# 100042155_3.net
KiCad netlist of a schematic drawn in EAGLE
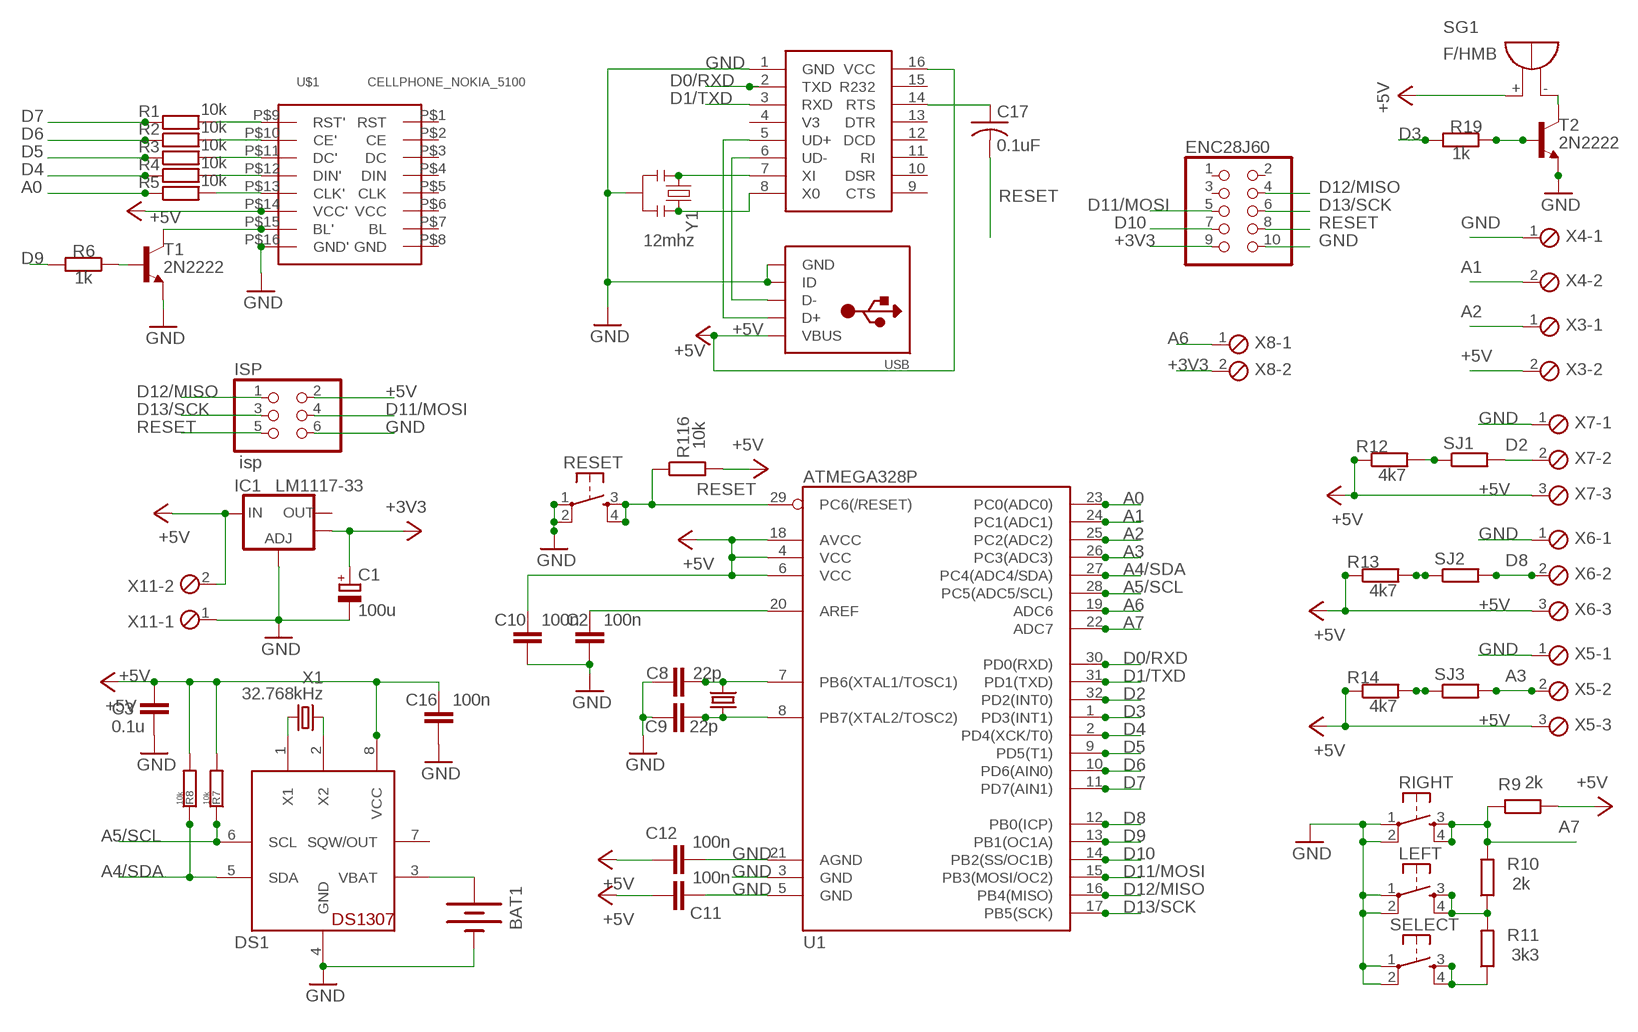
[diagram p0: schematic, sheet 1]

(export (version "E")
  (design (tool "Eeschema 10.0.6"))
  (components
    (comp (ref "BAT1")
      (value "BATTERY20PTH")
      (footprint "eagle-import:BATTCOM_20MM_PTH")
      (libsource (lib "eagle-import") (part "BATTERY20PTH"))
    )
    (comp (ref "C1")
      (value "100u")
      (footprint "eagle-import:E2-5")
      (libsource (lib "eagle-import") (part "CPOL-EUE2-5"))
    )
    (comp (ref "C2")
      (value "100n")
      (footprint "eagle-import:C0805")
      (libsource (lib "eagle-import") (part "resistor_C-EUC0805"))
    )
    (comp (ref "C3")
      (value "0.1u")
      (footprint "eagle-import:C0805")
      (libsource (lib "eagle-import") (part "C-EUC0805"))
    )
    (comp (ref "C8")
      (value "22p")
      (footprint "eagle-import:C0805")
      (libsource (lib "eagle-import") (part "resistor_C-EUC0805"))
    )
    (comp (ref "C9")
      (value "22p")
      (footprint "eagle-import:C0805")
      (libsource (lib "eagle-import") (part "resistor_C-EUC0805"))
    )
    (comp (ref "C10")
      (value "100n")
      (footprint "eagle-import:C0805")
      (libsource (lib "eagle-import") (part "resistor_C-EUC0805"))
    )
    (comp (ref "C11")
      (value "100n")
      (footprint "eagle-import:C0805")
      (libsource (lib "eagle-import") (part "resistor_C-EUC0805"))
    )
    (comp (ref "C12")
      (value "100n")
      (footprint "eagle-import:C0805")
      (libsource (lib "eagle-import") (part "resistor_C-EUC0805"))
    )
    (comp (ref "C16")
      (value "100n")
      (footprint "eagle-import:C0805")
      (libsource (lib "eagle-import") (part "resistor_C-EUC0805"))
    )
    (comp (ref "C17")
      (value "0.1uF")
      (footprint "eagle-import:C0805K")
      (libsource (lib "eagle-import") (part "C-USC0805K"))
    )
    (comp (ref "DS1")
      (value "DS1307")
      (footprint "eagle-import:SO08")
      (libsource (lib "eagle-import") (part "DS1307SOIC"))
    )
    (comp (ref "ENC28J60")
      (value "PINHD-2X5")
      (footprint "eagle-import:2X05")
      (libsource (lib "eagle-import") (part "PINHD-2X5"))
    )
    (comp (ref "IC1")
      (value "LM1117-33")
      (footprint "eagle-import:SOT223")
      (libsource (lib "eagle-import") (part "V_REG_LM1117SOT223"))
    )
    (comp (ref "ISP")
      (value "isp")
      (footprint "eagle-import:2X03")
      (libsource (lib "eagle-import") (part "PINHD-2X3"))
    )
    (comp (ref "LEFT")
      (value "TAC_SWITCHPTH")
      (footprint "eagle-import:TACTILE-PTH")
      (libsource (lib "eagle-import") (part "TAC_SWITCHPTH"))
    )
    (comp (ref "R1")
      (value "10k")
      (footprint "eagle-import:R0805")
      (libsource (lib "eagle-import") (part "R-EU_R0805"))
    )
    (comp (ref "R2")
      (value "10k")
      (footprint "eagle-import:R0805")
      (libsource (lib "eagle-import") (part "R-EU_R0805"))
    )
    (comp (ref "R3")
      (value "10k")
      (footprint "eagle-import:R0805")
      (libsource (lib "eagle-import") (part "R-EU_R0805"))
    )
    (comp (ref "R4")
      (value "10k")
      (footprint "eagle-import:R0805")
      (libsource (lib "eagle-import") (part "R-EU_R0805"))
    )
    (comp (ref "R5")
      (value "10k")
      (footprint "eagle-import:R0805")
      (libsource (lib "eagle-import") (part "R-EU_R0805"))
    )
    (comp (ref "R6")
      (value "1k")
      (footprint "eagle-import:R0805")
      (libsource (lib "eagle-import") (part "R-EU_R0805"))
    )
    (comp (ref "R7")
      (value "10k")
      (footprint "eagle-import:R0805")
      (libsource (lib "eagle-import") (part "R-EU_R0805"))
    )
    (comp (ref "R8")
      (value "10k")
      (footprint "eagle-import:R0805")
      (libsource (lib "eagle-import") (part "R-EU_R0805"))
    )
    (comp (ref "R9")
      (value "2k")
      (footprint "eagle-import:R0805")
      (libsource (lib "eagle-import") (part "R-EU_R0805"))
    )
    (comp (ref "R10")
      (value "2k")
      (footprint "eagle-import:R0805")
      (libsource (lib "eagle-import") (part "R-EU_R0805"))
    )
    (comp (ref "R11")
      (value "3k3")
      (footprint "eagle-import:R0805")
      (libsource (lib "eagle-import") (part "R-EU_R0805"))
    )
    (comp (ref "R12")
      (value "4k7")
      (footprint "eagle-import:R0805")
      (libsource (lib "eagle-import") (part "R-EU_R0805"))
    )
    (comp (ref "R13")
      (value "4k7")
      (footprint "eagle-import:R0805")
      (libsource (lib "eagle-import") (part "R-EU_R0805"))
    )
    (comp (ref "R14")
      (value "4k7")
      (footprint "eagle-import:R0805")
      (libsource (lib "eagle-import") (part "R-EU_R0805"))
    )
    (comp (ref "R19")
      (value "1k")
      (footprint "eagle-import:R0805")
      (libsource (lib "eagle-import") (part "R-EU_R0805"))
    )
    (comp (ref "R116")
      (value "10k")
      (footprint "eagle-import:R0805")
      (libsource (lib "eagle-import") (part "R-EU_R0805"))
    )
    (comp (ref "RESET")
      (value "TAC_SWITCHPTH")
      (footprint "eagle-import:TACTILE-PTH")
      (libsource (lib "eagle-import") (part "TAC_SWITCHPTH"))
    )
    (comp (ref "RIGHT")
      (value "TAC_SWITCHPTH")
      (footprint "eagle-import:TACTILE-PTH")
      (libsource (lib "eagle-import") (part "TAC_SWITCHPTH"))
    )
    (comp (ref "SELECT")
      (value "TAC_SWITCHPTH")
      (footprint "eagle-import:TACTILE-PTH")
      (libsource (lib "eagle-import") (part "TAC_SWITCHPTH"))
    )
    (comp (ref "SG1")
      (value "F/HMB")
      (footprint "eagle-import:F_HMB")
      (libsource (lib "eagle-import") (part "F/HMB"))
    )
    (comp (ref "SJ1")
      (value "R-EU_R0402")
      (footprint "eagle-import:R0402")
      (libsource (lib "eagle-import") (part "R-EU_R0402"))
    )
    (comp (ref "SJ2")
      (value "R-EU_R0402")
      (footprint "eagle-import:R0402")
      (libsource (lib "eagle-import") (part "R-EU_R0402"))
    )
    (comp (ref "SJ3")
      (value "R-EU_R0402")
      (footprint "eagle-import:R0402")
      (libsource (lib "eagle-import") (part "R-EU_R0402"))
    )
    (comp (ref "T1")
      (value "2N2222")
      (footprint "eagle-import:TO92-EBC-OVAL")
      (libsource (lib "eagle-import") (part "2N2222"))
    )
    (comp (ref "T2")
      (value "2N2222")
      (footprint "eagle-import:TO92-EBC-OVAL")
      (libsource (lib "eagle-import") (part "2N2222"))
    )
    (comp (ref "U$1")
      (value "CELLPHONE_NOKIA_5100")
      (footprint "eagle-import:CELLPHONE_NOKIA_5100_SPARKFUN")
      (libsource (lib "eagle-import") (part "CELLPHONE_NOKIA_5100"))
    )
    (comp (ref "U$2")
      (value "CH340G")
      (footprint "eagle-import:SO016")
      (libsource (lib "eagle-import") (part "CH340G"))
    )
    (comp (ref "U1")
      (value "ATMEGA328P")
      (footprint "eagle-import:TQFP32-08")
      (libsource (lib "eagle-import") (part "ATMEGA328_SMT"))
    )
    (comp (ref "USB")
      (value "USBMOLEX")
      (footprint "eagle-import:USB-MINIB-THM-MOLEX")
      (libsource (lib "eagle-import") (part "USBMOLEX"))
    )
    (comp (ref "X1")
      (value "32.768kHz")
      (footprint "eagle-import:TC26H")
      (libsource (lib "eagle-import") (part "crystal_CRYSTALTC26H"))
    )
    (comp (ref "X2")
      (value "16MHz")
      (footprint "eagle-import:HC49US")
      (libsource (lib "eagle-import") (part "CRYSTALHC49US"))
    )
    (comp (ref "X3")
      (value "MPT2")
      (footprint "eagle-import:2POL254")
      (libsource (lib "eagle-import") (part "MPT2"))
    )
    (comp (ref "X4")
      (value "MPT2")
      (footprint "eagle-import:2POL254")
      (libsource (lib "eagle-import") (part "MPT2"))
    )
    (comp (ref "X5")
      (value "MPT3")
      (footprint "eagle-import:3POL254")
      (libsource (lib "eagle-import") (part "MPT3"))
    )
    (comp (ref "X6")
      (value "MPT3")
      (footprint "eagle-import:3POL254")
      (libsource (lib "eagle-import") (part "MPT3"))
    )
    (comp (ref "X7")
      (value "MPT3")
      (footprint "eagle-import:3POL254")
      (libsource (lib "eagle-import") (part "MPT3"))
    )
    (comp (ref "X8")
      (value "MPT2")
      (footprint "eagle-import:2POL254")
      (libsource (lib "eagle-import") (part "MPT2"))
    )
    (comp (ref "X11")
      (value "MPT2")
      (footprint "eagle-import:2POL254")
      (fields (field (name "OC_FARNELL") "unknown") (field (name "OC_NEWARK") "unknown"))
      (libsource (lib "eagle-import") (part "MPT2"))
    )
    (comp (ref "Y1")
      (value "12mhz")
      (footprint "eagle-import:RESONATOR-PTH")
      (libsource (lib "eagle-import") (part "RESONATORPTH"))
    )
  )
  (nets
    (net (code "1") (name "+3V3") (class "Default")
      (node (ref "C1") (pin "+") (pinfunction "+_+") (pintype "passive"))
      (node (ref "ENC28J60") (pin "9") (pinfunction "9_9") (pintype "passive"))
      (node (ref "IC1") (pin "4") (pinfunction "OUT_4") (pintype "bidirectional"))
      (node (ref "X8") (pin "2") (pinfunction "1_2") (pintype "passive"))
    )
    (net (code "2") (name "+5V") (class "Default")
      (node (ref "C10") (pin "1") (pinfunction "1_1") (pintype "passive"))
      (node (ref "C11") (pin "2") (pinfunction "2_2") (pintype "passive"))
      (node (ref "C12") (pin "2") (pinfunction "2_2") (pintype "passive"))
      (node (ref "C16") (pin "1") (pinfunction "1_1") (pintype "passive"))
      (node (ref "C3") (pin "1") (pinfunction "1_1") (pintype "passive"))
      (node (ref "DS1") (pin "8") (pinfunction "VCC_8") (pintype "power_in"))
      (node (ref "IC1") (pin "3") (pinfunction "IN_3") (pintype "input"))
      (node (ref "ISP") (pin "2") (pinfunction "2_2") (pintype "passive"))
      (node (ref "R116") (pin "2") (pinfunction "2_2") (pintype "passive"))
      (node (ref "R12") (pin "1") (pinfunction "1_1") (pintype "passive"))
      (node (ref "R13") (pin "1") (pinfunction "1_1") (pintype "passive"))
      (node (ref "R14") (pin "1") (pinfunction "1_1") (pintype "passive"))
      (node (ref "R7") (pin "2") (pinfunction "2_2") (pintype "passive"))
      (node (ref "R8") (pin "2") (pinfunction "2_2") (pintype "passive"))
      (node (ref "R9") (pin "2") (pinfunction "2_2") (pintype "passive"))
      (node (ref "SG1") (pin "+") (pinfunction "+_+") (pintype "passive"))
      (node (ref "U$1") (pin "P$14") (pinfunction "VCC'_P$14") (pintype "bidirectional"))
      (node (ref "U$2") (pin "16") (pinfunction "VCC_16") (pintype "bidirectional"))
      (node (ref "U1") (pin "18") (pinfunction "AVCC_18") (pintype "bidirectional"))
      (node (ref "U1") (pin "4") (pinfunction "VCC_4") (pintype "bidirectional"))
      (node (ref "U1") (pin "6") (pinfunction "VCC_6") (pintype "bidirectional"))
      (node (ref "USB") (pin "VBUS") (pinfunction "VBUS_VBUS") (pintype "power_in"))
      (node (ref "X11") (pin "2") (pinfunction "1_2") (pintype "passive"))
      (node (ref "X3") (pin "2") (pinfunction "1_2") (pintype "passive"))
      (node (ref "X5") (pin "3") (pinfunction "1_3") (pintype "passive"))
      (node (ref "X6") (pin "3") (pinfunction "1_3") (pintype "passive"))
      (node (ref "X7") (pin "3") (pinfunction "1_3") (pintype "passive"))
    )
    (net (code "3") (name "/A0") (class "Default")
      (node (ref "R5") (pin "1") (pinfunction "1_1") (pintype "passive"))
      (node (ref "U1") (pin "23") (pinfunction "PC0(ADC0)_23") (pintype "bidirectional"))
    )
    (net (code "4") (name "/A1") (class "Default")
      (node (ref "U1") (pin "24") (pinfunction "PC1(ADC1)_24") (pintype "bidirectional"))
      (node (ref "X4") (pin "2") (pinfunction "1_2") (pintype "passive"))
    )
    (net (code "5") (name "/A2") (class "Default")
      (node (ref "U1") (pin "25") (pinfunction "PC2(ADC2)_25") (pintype "bidirectional"))
      (node (ref "X3") (pin "1") (pinfunction "1_1") (pintype "passive"))
    )
    (net (code "6") (name "/A3") (class "Default")
      (node (ref "SJ3") (pin "2") (pinfunction "2_2") (pintype "passive"))
      (node (ref "U1") (pin "26") (pinfunction "PC3(ADC3)_26") (pintype "bidirectional"))
      (node (ref "X5") (pin "2") (pinfunction "1_2") (pintype "passive"))
    )
    (net (code "7") (name "/A4{slash}SDA") (class "Default")
      (node (ref "DS1") (pin "5") (pinfunction "SDA_5") (pintype "bidirectional"))
      (node (ref "R8") (pin "1") (pinfunction "1_1") (pintype "passive"))
      (node (ref "U1") (pin "27") (pinfunction "PC4(ADC4/SDA)_27") (pintype "bidirectional"))
    )
    (net (code "8") (name "/A5{slash}SCL") (class "Default")
      (node (ref "DS1") (pin "6") (pinfunction "SCL_6") (pintype "bidirectional"))
      (node (ref "R7") (pin "1") (pinfunction "1_1") (pintype "passive"))
      (node (ref "U1") (pin "28") (pinfunction "PC5(ADC5/SCL)_28") (pintype "bidirectional"))
    )
    (net (code "9") (name "/A6") (class "Default")
      (node (ref "U1") (pin "19") (pinfunction "ADC6_19") (pintype "bidirectional"))
      (node (ref "X8") (pin "1") (pinfunction "1_1") (pintype "passive"))
    )
    (net (code "10") (name "/A7") (class "Default")
      (node (ref "R10") (pin "2") (pinfunction "2_2") (pintype "passive"))
      (node (ref "R9") (pin "1") (pinfunction "1_1") (pintype "passive"))
      (node (ref "RIGHT") (pin "3") (pinfunction "3_3") (pintype "passive"))
      (node (ref "RIGHT") (pin "4") (pinfunction "4_4") (pintype "passive"))
      (node (ref "U1") (pin "22") (pinfunction "ADC7_22") (pintype "bidirectional"))
    )
    (net (code "11") (name "/D0{slash}RXD") (class "Default")
      (node (ref "U$2") (pin "2") (pinfunction "TXD_2") (pintype "bidirectional"))
      (node (ref "U1") (pin "30") (pinfunction "PD0(RXD)_30") (pintype "bidirectional"))
    )
    (net (code "12") (name "/D1{slash}TXD") (class "Default")
      (node (ref "U$2") (pin "3") (pinfunction "RXD_3") (pintype "bidirectional"))
      (node (ref "U1") (pin "31") (pinfunction "PD1(TXD)_31") (pintype "bidirectional"))
    )
    (net (code "13") (name "/D2") (class "Default")
      (node (ref "SJ1") (pin "2") (pinfunction "2_2") (pintype "passive"))
      (node (ref "U1") (pin "32") (pinfunction "PD2(INT0)_32") (pintype "bidirectional"))
      (node (ref "X7") (pin "2") (pinfunction "1_2") (pintype "passive"))
    )
    (net (code "14") (name "/D3") (class "Default")
      (node (ref "R19") (pin "2") (pinfunction "2_2") (pintype "passive"))
      (node (ref "U1") (pin "1") (pinfunction "PD3(INT1)_1") (pintype "bidirectional"))
    )
    (net (code "15") (name "/D4") (class "Default")
      (node (ref "R4") (pin "1") (pinfunction "1_1") (pintype "passive"))
      (node (ref "U1") (pin "2") (pinfunction "PD4(XCK/T0)_2") (pintype "bidirectional"))
    )
    (net (code "16") (name "/D5") (class "Default")
      (node (ref "R3") (pin "1") (pinfunction "1_1") (pintype "passive"))
      (node (ref "U1") (pin "9") (pinfunction "PD5(T1)_9") (pintype "bidirectional"))
    )
    (net (code "17") (name "/D6") (class "Default")
      (node (ref "R2") (pin "1") (pinfunction "1_1") (pintype "passive"))
      (node (ref "U1") (pin "10") (pinfunction "PD6(AIN0)_10") (pintype "bidirectional"))
    )
    (net (code "18") (name "/D7") (class "Default")
      (node (ref "R1") (pin "1") (pinfunction "1_1") (pintype "passive"))
      (node (ref "U1") (pin "11") (pinfunction "PD7(AIN1)_11") (pintype "bidirectional"))
    )
    (net (code "19") (name "/D8") (class "Default")
      (node (ref "SJ2") (pin "2") (pinfunction "2_2") (pintype "passive"))
      (node (ref "U1") (pin "12") (pinfunction "PB0(ICP)_12") (pintype "bidirectional"))
      (node (ref "X6") (pin "2") (pinfunction "1_2") (pintype "passive"))
    )
    (net (code "20") (name "/D9") (class "Default")
      (node (ref "R6") (pin "2") (pinfunction "2_2") (pintype "passive"))
      (node (ref "U1") (pin "13") (pinfunction "PB1(OC1A)_13") (pintype "bidirectional"))
    )
    (net (code "21") (name "/D10") (class "Default")
      (node (ref "ENC28J60") (pin "7") (pinfunction "7_7") (pintype "passive"))
      (node (ref "U1") (pin "14") (pinfunction "PB2(SS/OC1B)_14") (pintype "bidirectional"))
    )
    (net (code "22") (name "/D11{slash}MOSI") (class "Default")
      (node (ref "ENC28J60") (pin "5") (pinfunction "5_5") (pintype "passive"))
      (node (ref "ISP") (pin "4") (pinfunction "4_4") (pintype "passive"))
      (node (ref "U1") (pin "15") (pinfunction "PB3(MOSI/OC2)_15") (pintype "bidirectional"))
    )
    (net (code "23") (name "/D12{slash}MISO") (class "Default")
      (node (ref "ENC28J60") (pin "4") (pinfunction "4_4") (pintype "passive"))
      (node (ref "ISP") (pin "1") (pinfunction "1_1") (pintype "passive"))
      (node (ref "U1") (pin "16") (pinfunction "PB4(MISO)_16") (pintype "bidirectional"))
    )
    (net (code "24") (name "/D13{slash}SCK") (class "Default")
      (node (ref "ENC28J60") (pin "6") (pinfunction "6_6") (pintype "passive"))
      (node (ref "ISP") (pin "3") (pinfunction "3_3") (pintype "passive"))
      (node (ref "U1") (pin "17") (pinfunction "PB5(SCK)_17") (pintype "bidirectional"))
    )
    (net (code "25") (name "/RESET") (class "Default")
      (node (ref "C17") (pin "2") (pinfunction "2_2") (pintype "passive"))
      (node (ref "ENC28J60") (pin "8") (pinfunction "8_8") (pintype "passive"))
      (node (ref "ISP") (pin "5") (pinfunction "5_5") (pintype "passive"))
      (node (ref "R116") (pin "1") (pinfunction "1_1") (pintype "passive"))
      (node (ref "RESET") (pin "3") (pinfunction "3_3") (pintype "passive"))
      (node (ref "RESET") (pin "4") (pinfunction "4_4") (pintype "passive"))
      (node (ref "U1") (pin "29") (pinfunction "PC6(/RESET)_29") (pintype "bidirectional"))
    )
    (net (code "26") (name "GND") (class "Default")
      (node (ref "BAT1") (pin "2") (pinfunction "-_2") (pintype "power_in"))
      (node (ref "C1") (pin "-") (pinfunction "-_-") (pintype "passive"))
      (node (ref "C10") (pin "2") (pinfunction "2_2") (pintype "passive"))
      (node (ref "C11") (pin "1") (pinfunction "1_1") (pintype "passive"))
      (node (ref "C12") (pin "1") (pinfunction "1_1") (pintype "passive"))
      (node (ref "C16") (pin "2") (pinfunction "2_2") (pintype "passive"))
      (node (ref "C2") (pin "2") (pinfunction "2_2") (pintype "passive"))
      (node (ref "C3") (pin "2") (pinfunction "2_2") (pintype "passive"))
      (node (ref "C8") (pin "1") (pinfunction "1_1") (pintype "passive"))
      (node (ref "C9") (pin "1") (pinfunction "1_1") (pintype "passive"))
      (node (ref "DS1") (pin "4") (pinfunction "GND_4") (pintype "power_in"))
      (node (ref "ENC28J60") (pin "10") (pinfunction "10_10") (pintype "passive"))
      (node (ref "IC1") (pin "1") (pinfunction "ADJ_1") (pintype "input"))
      (node (ref "ISP") (pin "6") (pinfunction "6_6") (pintype "passive"))
      (node (ref "LEFT") (pin "1") (pinfunction "1_1") (pintype "passive"))
      (node (ref "LEFT") (pin "2") (pinfunction "2_2") (pintype "passive"))
      (node (ref "RESET") (pin "1") (pinfunction "1_1") (pintype "passive"))
      (node (ref "RESET") (pin "2") (pinfunction "2_2") (pintype "passive"))
      (node (ref "RIGHT") (pin "1") (pinfunction "1_1") (pintype "passive"))
      (node (ref "RIGHT") (pin "2") (pinfunction "2_2") (pintype "passive"))
      (node (ref "SELECT") (pin "1") (pinfunction "1_1") (pintype "passive"))
      (node (ref "SELECT") (pin "2") (pinfunction "2_2") (pintype "passive"))
      (node (ref "T1") (pin "E") (pinfunction "E_E") (pintype "passive"))
      (node (ref "T2") (pin "E") (pinfunction "E_E") (pintype "passive"))
      (node (ref "U$1") (pin "P$16") (pinfunction "GND'_P$16") (pintype "bidirectional"))
      (node (ref "U$2") (pin "1") (pinfunction "GND_1") (pintype "bidirectional"))
      (node (ref "U1") (pin "21") (pinfunction "AGND_21") (pintype "bidirectional"))
      (node (ref "U1") (pin "3") (pinfunction "GND_3") (pintype "bidirectional"))
      (node (ref "U1") (pin "5") (pinfunction "GND_5") (pintype "bidirectional"))
      (node (ref "USB") (pin "GND") (pinfunction "GND_GND") (pintype "power_in"))
      (node (ref "USB") (pin "ID") (pinfunction "ID_ID") (pintype "bidirectional"))
      (node (ref "X11") (pin "1") (pinfunction "1_1") (pintype "passive"))
      (node (ref "X4") (pin "1") (pinfunction "1_1") (pintype "passive"))
      (node (ref "X5") (pin "1") (pinfunction "1_1") (pintype "passive"))
      (node (ref "X6") (pin "1") (pinfunction "1_1") (pintype "passive"))
      (node (ref "X7") (pin "1") (pinfunction "1_1") (pintype "passive"))
      (node (ref "Y1") (pin "2") (pinfunction "2_2") (pintype "passive"))
    )
    (net (code "27") (name "Net-(BAT1-+)") (class "Default")
      (node (ref "BAT1") (pin "1") (pinfunction "+_1") (pintype "power_in"))
      (node (ref "DS1") (pin "3") (pinfunction "VBAT_3") (pintype "power_in"))
    )
    (net (code "28") (name "Net-(DS1-X1)") (class "Default")
      (node (ref "DS1") (pin "1") (pinfunction "X1_1") (pintype "passive"))
      (node (ref "X1") (pin "2") (pinfunction "2_2") (pintype "passive"))
    )
    (net (code "29") (name "Net-(DS1-X2)") (class "Default")
      (node (ref "DS1") (pin "2") (pinfunction "X2_2") (pintype "passive"))
      (node (ref "X1") (pin "1") (pinfunction "1_1") (pintype "passive"))
    )
    (net (code "30") (name "Net-(LEFT-Pad3)") (class "Default")
      (node (ref "LEFT") (pin "3") (pinfunction "3_3") (pintype "passive"))
      (node (ref "LEFT") (pin "4") (pinfunction "4_4") (pintype "passive"))
      (node (ref "R10") (pin "1") (pinfunction "1_1") (pintype "passive"))
      (node (ref "R11") (pin "2") (pinfunction "2_2") (pintype "passive"))
    )
    (net (code "31") (name "Net-(R6-Pad1)") (class "Default")
      (node (ref "R6") (pin "1") (pinfunction "1_1") (pintype "passive"))
      (node (ref "T1") (pin "B") (pinfunction "B_B") (pintype "passive"))
    )
    (net (code "32") (name "Net-(R11-Pad1)") (class "Default")
      (node (ref "R11") (pin "1") (pinfunction "1_1") (pintype "passive"))
      (node (ref "SELECT") (pin "3") (pinfunction "3_3") (pintype "passive"))
      (node (ref "SELECT") (pin "4") (pinfunction "4_4") (pintype "passive"))
    )
    (net (code "33") (name "Net-(R12-Pad2)") (class "Default")
      (node (ref "R12") (pin "2") (pinfunction "2_2") (pintype "passive"))
      (node (ref "SJ1") (pin "1") (pinfunction "1_1") (pintype "passive"))
    )
    (net (code "34") (name "Net-(R13-Pad2)") (class "Default")
      (node (ref "R13") (pin "2") (pinfunction "2_2") (pintype "passive"))
      (node (ref "SJ2") (pin "1") (pinfunction "1_1") (pintype "passive"))
    )
    (net (code "35") (name "Net-(R14-Pad2)") (class "Default")
      (node (ref "R14") (pin "2") (pinfunction "2_2") (pintype "passive"))
      (node (ref "SJ3") (pin "1") (pinfunction "1_1") (pintype "passive"))
    )
    (net (code "36") (name "Net-(R19-Pad1)") (class "Default")
      (node (ref "R19") (pin "1") (pinfunction "1_1") (pintype "passive"))
      (node (ref "T2") (pin "B") (pinfunction "B_B") (pintype "passive"))
    )
    (net (code "37") (name "Net-(SG1-Pad-)") (class "Default")
      (node (ref "SG1") (pin "-") (pinfunction "-_-") (pintype "passive"))
      (node (ref "T2") (pin "C") (pinfunction "C_C") (pintype "passive"))
    )
    (net (code "38") (name "Net-(U$1-BL')") (class "Default")
      (node (ref "T1") (pin "C") (pinfunction "C_C") (pintype "passive"))
      (node (ref "U$1") (pin "P$15") (pinfunction "BL'_P$15") (pintype "bidirectional"))
    )
    (net (code "39") (name "Net-(U$1-CE')") (class "Default")
      (node (ref "R2") (pin "2") (pinfunction "2_2") (pintype "passive"))
      (node (ref "U$1") (pin "P$10") (pinfunction "CE'_P$10") (pintype "bidirectional"))
    )
    (net (code "40") (name "Net-(U$1-CLK')") (class "Default")
      (node (ref "R5") (pin "2") (pinfunction "2_2") (pintype "passive"))
      (node (ref "U$1") (pin "P$13") (pinfunction "CLK'_P$13") (pintype "bidirectional"))
    )
    (net (code "41") (name "Net-(U$1-DC')") (class "Default")
      (node (ref "R3") (pin "2") (pinfunction "2_2") (pintype "passive"))
      (node (ref "U$1") (pin "P$11") (pinfunction "DC'_P$11") (pintype "bidirectional"))
    )
    (net (code "42") (name "Net-(U$1-DIN')") (class "Default")
      (node (ref "R4") (pin "2") (pinfunction "2_2") (pintype "passive"))
      (node (ref "U$1") (pin "P$12") (pinfunction "DIN'_P$12") (pintype "bidirectional"))
    )
    (net (code "43") (name "Net-(U$1-RST')") (class "Default")
      (node (ref "R1") (pin "2") (pinfunction "2_2") (pintype "passive"))
      (node (ref "U$1") (pin "P$9") (pinfunction "RST'_P$9") (pintype "bidirectional"))
    )
    (net (code "44") (name "Net-(U$2-RTS)") (class "Default")
      (node (ref "C17") (pin "1") (pinfunction "1_1") (pintype "passive"))
      (node (ref "U$2") (pin "14") (pinfunction "RTS_14") (pintype "bidirectional"))
    )
    (net (code "45") (name "Net-(U$2-UD+)") (class "Default")
      (node (ref "U$2") (pin "5") (pinfunction "UD+_5") (pintype "bidirectional"))
      (node (ref "USB") (pin "D+") (pinfunction "D+_D+") (pintype "bidirectional"))
    )
    (net (code "46") (name "Net-(U$2-UD-)") (class "Default")
      (node (ref "U$2") (pin "6") (pinfunction "UD-_6") (pintype "bidirectional"))
      (node (ref "USB") (pin "D-") (pinfunction "D-_D-") (pintype "bidirectional"))
    )
    (net (code "47") (name "Net-(U$2-X0)") (class "Default")
      (node (ref "U$2") (pin "8") (pinfunction "X0_8") (pintype "bidirectional"))
      (node (ref "Y1") (pin "3") (pinfunction "3_3") (pintype "passive"))
    )
    (net (code "48") (name "Net-(U$2-XI)") (class "Default")
      (node (ref "U$2") (pin "7") (pinfunction "XI_7") (pintype "bidirectional"))
      (node (ref "Y1") (pin "1") (pinfunction "1_1") (pintype "passive"))
    )
    (net (code "49") (name "Net-(U1-AREF)") (class "Default")
      (node (ref "C2") (pin "1") (pinfunction "1_1") (pintype "passive"))
      (node (ref "U1") (pin "20") (pinfunction "AREF_20") (pintype "bidirectional"))
    )
    (net (code "50") (name "Net-(U1-PB6(XTAL1{slash}TOSC1))") (class "Default")
      (node (ref "C8") (pin "2") (pinfunction "2_2") (pintype "passive"))
      (node (ref "U1") (pin "7") (pinfunction "PB6(XTAL1/TOSC1)_7") (pintype "bidirectional"))
      (node (ref "X2") (pin "2") (pinfunction "2_2") (pintype "passive"))
    )
    (net (code "51") (name "Net-(U1-PB7(XTAL2{slash}TOSC2))") (class "Default")
      (node (ref "C9") (pin "2") (pinfunction "2_2") (pintype "passive"))
      (node (ref "U1") (pin "8") (pinfunction "PB7(XTAL2/TOSC2)_8") (pintype "bidirectional"))
      (node (ref "X2") (pin "1") (pinfunction "1_1") (pintype "passive"))
    )
    (net (code "52") (name "unconnected-(DS1-SQW{slash}OUT-Pad7)") (class "Default")
      (node (ref "DS1") (pin "7") (pinfunction "SQW/OUT_7") (pintype "bidirectional"))
    )
    (net (code "53") (name "unconnected-(ENC28J60-Pad1)") (class "Default")
      (node (ref "ENC28J60") (pin "1") (pinfunction "1_1") (pintype "passive"))
    )
    (net (code "54") (name "unconnected-(ENC28J60-Pad2)") (class "Default")
      (node (ref "ENC28J60") (pin "2") (pinfunction "2_2") (pintype "passive"))
    )
    (net (code "55") (name "unconnected-(ENC28J60-Pad3)") (class "Default")
      (node (ref "ENC28J60") (pin "3") (pinfunction "3_3") (pintype "passive"))
    )
    (net (code "56") (name "unconnected-(IC1-OUT-Pad2)") (class "Default")
      (node (ref "IC1") (pin "2") (pinfunction "OUT_2") (pintype "bidirectional"))
    )
    (net (code "57") (name "unconnected-(U$1-BL-PadP$7)") (class "Default")
      (node (ref "U$1") (pin "P$7") (pinfunction "BL_P$7") (pintype "bidirectional"))
    )
    (net (code "58") (name "unconnected-(U$1-CE-PadP$2)") (class "Default")
      (node (ref "U$1") (pin "P$2") (pinfunction "CE_P$2") (pintype "bidirectional"))
    )
    (net (code "59") (name "unconnected-(U$1-CLK-PadP$5)") (class "Default")
      (node (ref "U$1") (pin "P$5") (pinfunction "CLK_P$5") (pintype "bidirectional"))
    )
    (net (code "60") (name "unconnected-(U$1-DC-PadP$3)") (class "Default")
      (node (ref "U$1") (pin "P$3") (pinfunction "DC_P$3") (pintype "bidirectional"))
    )
    (net (code "61") (name "unconnected-(U$1-DIN-PadP$4)") (class "Default")
      (node (ref "U$1") (pin "P$4") (pinfunction "DIN_P$4") (pintype "bidirectional"))
    )
    (net (code "62") (name "unconnected-(U$1-GND-PadP$8)") (class "Default")
      (node (ref "U$1") (pin "P$8") (pinfunction "GND_P$8") (pintype "bidirectional"))
    )
    (net (code "63") (name "unconnected-(U$1-RST-PadP$1)") (class "Default")
      (node (ref "U$1") (pin "P$1") (pinfunction "RST_P$1") (pintype "bidirectional"))
    )
    (net (code "64") (name "unconnected-(U$1-VCC-PadP$6)") (class "Default")
      (node (ref "U$1") (pin "P$6") (pinfunction "VCC_P$6") (pintype "bidirectional"))
    )
    (net (code "65") (name "unconnected-(U$2-CTS-Pad9)") (class "Default")
      (node (ref "U$2") (pin "9") (pinfunction "CTS_9") (pintype "bidirectional"))
    )
    (net (code "66") (name "unconnected-(U$2-DCD-Pad12)") (class "Default")
      (node (ref "U$2") (pin "12") (pinfunction "DCD_12") (pintype "bidirectional"))
    )
    (net (code "67") (name "unconnected-(U$2-DSR-Pad10)") (class "Default")
      (node (ref "U$2") (pin "10") (pinfunction "DSR_10") (pintype "bidirectional"))
    )
    (net (code "68") (name "unconnected-(U$2-DTR-Pad13)") (class "Default")
      (node (ref "U$2") (pin "13") (pinfunction "DTR_13") (pintype "bidirectional"))
    )
    (net (code "69") (name "unconnected-(U$2-R232-Pad15)") (class "Default")
      (node (ref "U$2") (pin "15") (pinfunction "R232_15") (pintype "bidirectional"))
    )
    (net (code "70") (name "unconnected-(U$2-RI-Pad11)") (class "Default")
      (node (ref "U$2") (pin "11") (pinfunction "RI_11") (pintype "bidirectional"))
    )
    (net (code "71") (name "unconnected-(U$2-V3-Pad4)") (class "Default")
      (node (ref "U$2") (pin "4") (pinfunction "V3_4") (pintype "bidirectional"))
    )
  )
)
